# jarit__paneli.net
KiCad netlist of a schematic drawn in Altium Designer
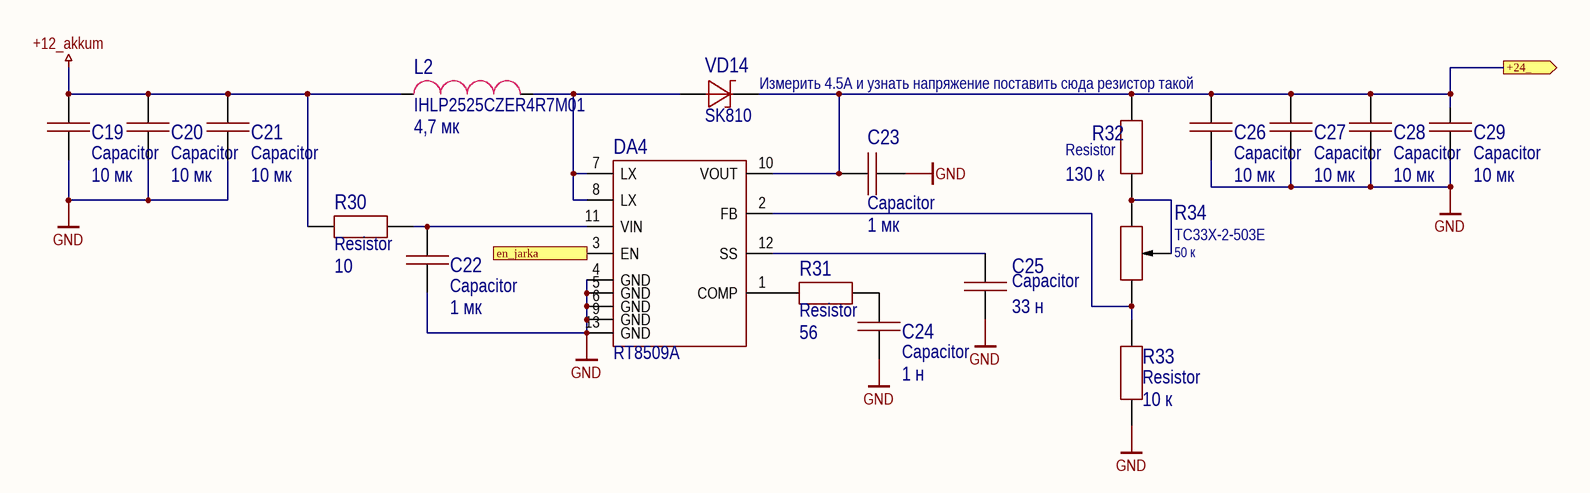
[diagram p0: jarit'_paneli.SchDoc]

(export (version "E")
  (design (tool "Eeschema 10.0.6"))
  (components
    (comp (ref "C19")
      (value "Capacitor")
      (footprint "1210C")
      (description "Конденсатор")
      (fields
        (field (name "ALTIUM_VALUE") "10 мк")
        (field (name "PART NUMBER") "Capacitor_10u_10_35V_X7R_1210C")
        (field (name "TOLERANCE") "0,1")
      )
      (libsource (lib "Hydrolib") (part "Capacitor"))
    )
    (comp (ref "C20")
      (value "Capacitor")
      (footprint "1210C")
      (description "Конденсатор")
      (fields
        (field (name "ALTIUM_VALUE") "10 мк")
        (field (name "PART NUMBER") "Capacitor_10u_10_35V_X7R_1210C")
        (field (name "TOLERANCE") "0,1")
      )
      (libsource (lib "Hydrolib") (part "Capacitor"))
    )
    (comp (ref "C21")
      (value "Capacitor")
      (footprint "1210C")
      (description "Конденсатор")
      (fields
        (field (name "ALTIUM_VALUE") "10 мк")
        (field (name "PART NUMBER") "Capacitor_10u_10_35V_X7R_1210C")
        (field (name "TOLERANCE") "0,1")
      )
      (libsource (lib "Hydrolib") (part "Capacitor"))
    )
    (comp (ref "C22")
      (value "Capacitor")
      (footprint "0603C")
      (description "Конденсатор")
      (fields
        (field (name "ALTIUM_VALUE") "1 мк")
        (field (name "PART NUMBER") "Capacitor_1u_10_50V_X7R_0603C")
        (field (name "TOLERANCE") "0,1")
      )
      (libsource (lib "Hydrolib") (part "Capacitor"))
    )
    (comp (ref "C23")
      (value "Capacitor")
      (footprint "0603C")
      (description "Конденсатор")
      (fields
        (field (name "ALTIUM_VALUE") "1 мк")
        (field (name "PART NUMBER") "Capacitor_1u_10_50V_X7R_0603C")
        (field (name "TOLERANCE") "0,1")
      )
      (libsource (lib "Hydrolib") (part "Capacitor"))
    )
    (comp (ref "C24")
      (value "Capacitor")
      (footprint "0603C")
      (description "Конденсатор")
      (fields
        (field (name "ALTIUM_VALUE") "1 н")
        (field (name "PART NUMBER") "Capacitor_1n_10_50V_X7R_0603C")
        (field (name "TOLERANCE") "0,1")
      )
      (libsource (lib "Hydrolib") (part "Capacitor"))
    )
    (comp (ref "C25")
      (value "Capacitor")
      (footprint "0603C")
      (description "Конденсатор")
      (fields
        (field (name "ALTIUM_VALUE") "33 н")
        (field (name "PART NUMBER") "Capacitor_33n_10_50V_X7R_0603C")
        (field (name "TOLERANCE") "0,1")
      )
      (libsource (lib "Hydrolib") (part "Capacitor"))
    )
    (comp (ref "C26")
      (value "Capacitor")
      (footprint "1210C")
      (description "Конденсатор")
      (fields
        (field (name "ALTIUM_VALUE") "10 мк")
        (field (name "PART NUMBER") "Capacitor_10u_10_35V_X7R_1210C")
        (field (name "TOLERANCE") "0,1")
      )
      (libsource (lib "Hydrolib") (part "Capacitor"))
    )
    (comp (ref "C27")
      (value "Capacitor")
      (footprint "1210C")
      (description "Конденсатор")
      (fields
        (field (name "ALTIUM_VALUE") "10 мк")
        (field (name "PART NUMBER") "Capacitor_10u_10_35V_X7R_1210C")
        (field (name "TOLERANCE") "0,1")
      )
      (libsource (lib "Hydrolib") (part "Capacitor"))
    )
    (comp (ref "C28")
      (value "Capacitor")
      (footprint "1210C")
      (description "Конденсатор")
      (fields
        (field (name "ALTIUM_VALUE") "10 мк")
        (field (name "PART NUMBER") "Capacitor_10u_10_35V_X7R_1210C")
        (field (name "TOLERANCE") "0,1")
      )
      (libsource (lib "Hydrolib") (part "Capacitor"))
    )
    (comp (ref "C29")
      (value "Capacitor")
      (footprint "1210C")
      (description "Конденсатор")
      (fields
        (field (name "ALTIUM_VALUE") "10 мк")
        (field (name "PART NUMBER") "Capacitor_10u_10_35V_X7R_1210C")
        (field (name "TOLERANCE") "0,1")
      )
      (libsource (lib "Hydrolib") (part "Capacitor"))
    )
    (comp (ref "DA4")
      (value "RT8509A")
      (footprint "WDFN5x5-12")
      (description "Импульсный повышающий DC-DC стабилизатор, регулируемый, 2.8В-14В (Vin), 24В/4.5A, 1.5МГц, WDFN-12")
      (libsource (lib "Hydrolib") (part "RT8509A"))
    )
    (comp (ref "L2")
      (value "IHLP2525CZER4R7M01")
      (footprint "IHLP-2525")
      (description "ЧИП-индуктивность экранированная 4,7мкГн ±20% 5,5A 40мОм 2525")
      (fields (field (name "ALTIUM_VALUE") "4,7 мк"))
      (libsource (lib "Hydrolib") (part "Inductance"))
    )
    (comp (ref "R30")
      (value "Resistor")
      (footprint "0603R")
      (description "Резистор номиналом 10 Ом и точностью 1%")
      (fields
        (field (name "ALTIUM_VALUE") "10")
        (field (name "PART NUMBER") "Resistor_10_1_0603")
        (field (name "TOLERANCE") "1%")
      )
      (libsource (lib "") (part "Resistor_2"))
    )
    (comp (ref "R31")
      (value "Resistor")
      (footprint "0603R")
      (description "Резистор номиналом 56 Ом и точностью 1%")
      (fields
        (field (name "ALTIUM_VALUE") "56")
        (field (name "PART NUMBER") "Resistor_56_1_0603")
        (field (name "TOLERANCE") "1%")
      )
      (libsource (lib "") (part "Resistor_1"))
    )
    (comp (ref "R32")
      (value "Resistor")
      (footprint "0603R")
      (description "Резистор номиналом 130 кОм и точностью 1%")
      (fields
        (field (name "ALTIUM_VALUE") "130 к")
        (field (name "PART NUMBER") "Resistor_130k_1_0603")
        (field (name "TOLERANCE") "1%")
      )
      (libsource (lib "") (part "Resistor_3"))
    )
    (comp (ref "R33")
      (value "Resistor")
      (footprint "0603R")
      (description "Резистор номиналом 10 кОм и точностью 1%")
      (fields
        (field (name "ALTIUM_VALUE") "10 к")
        (field (name "PART NUMBER") "Resistor_10k_1_0603")
        (field (name "TOLERANCE") "1%")
      )
      (libsource (lib "Hydrolib") (part "Resistor"))
    )
    (comp (ref "R34")
      (value "TC33X-2-503E")
      (footprint "3mm_trim")
      (description "Потенциометр однооборотный керметный 50кОм 0.1Вт ±25% SMD лента на катушке")
      (fields (field (name "ALTIUM_VALUE") "50 к") (field (name "TOLERANCE") "50%"))
      (libsource (lib "Hydrolib") (part "trim_res"))
    )
    (comp (ref "VD14")
      (value "SK810")
      (footprint "SMC")
      (description "Диод шоттки на 100 В, ном. ток 8 А")
      (libsource (lib "Hydrolib") (part "Schottky_diode"))
    )
  )
  (nets
    (net (code "1") (name "+12_akkum") (class "Default")
      (node (ref "C19") (pin "2") (pinfunction "2_2") (pintype "passive"))
      (node (ref "C20") (pin "2") (pinfunction "2_2") (pintype "passive"))
      (node (ref "C21") (pin "2") (pinfunction "2_2") (pintype "passive"))
      (node (ref "L2") (pin "1") (pinfunction "1_1") (pintype "passive"))
      (node (ref "R30") (pin "2") (pinfunction "2_2") (pintype "passive"))
    )
    (net (code "2") (name "/+24_") (class "Default")
      (node (ref "C23") (pin "1") (pinfunction "1_1") (pintype "passive"))
      (node (ref "C26") (pin "2") (pinfunction "2_2") (pintype "passive"))
      (node (ref "C27") (pin "2") (pinfunction "2_2") (pintype "passive"))
      (node (ref "C28") (pin "2") (pinfunction "2_2") (pintype "passive"))
      (node (ref "C29") (pin "2") (pinfunction "2_2") (pintype "passive"))
      (node (ref "DA4") (pin "10") (pinfunction "VOUT_10") (pintype "passive"))
      (node (ref "R32") (pin "2") (pinfunction "2_2") (pintype "passive"))
      (node (ref "VD14") (pin "2") (pinfunction "2_2") (pintype "passive"))
    )
    (net (code "3") (name "/en_jarka") (class "Default")
      (node (ref "DA4") (pin "3") (pinfunction "EN_3") (pintype "passive"))
    )
    (net (code "4") (name "GND") (class "Default")
      (node (ref "C19") (pin "1") (pinfunction "1_1") (pintype "passive"))
      (node (ref "C20") (pin "1") (pinfunction "1_1") (pintype "passive"))
      (node (ref "C21") (pin "1") (pinfunction "1_1") (pintype "passive"))
      (node (ref "C22") (pin "1") (pinfunction "1_1") (pintype "passive"))
      (node (ref "C23") (pin "2") (pinfunction "2_2") (pintype "passive"))
      (node (ref "C24") (pin "1") (pinfunction "1_1") (pintype "passive"))
      (node (ref "C25") (pin "2") (pinfunction "2_2") (pintype "passive"))
      (node (ref "C26") (pin "1") (pinfunction "1_1") (pintype "passive"))
      (node (ref "C27") (pin "1") (pinfunction "1_1") (pintype "passive"))
      (node (ref "C28") (pin "1") (pinfunction "1_1") (pintype "passive"))
      (node (ref "C29") (pin "1") (pinfunction "1_1") (pintype "passive"))
      (node (ref "DA4") (pin "13") (pinfunction "GND_13") (pintype "passive"))
      (node (ref "DA4") (pin "4") (pinfunction "GND_4") (pintype "passive"))
      (node (ref "DA4") (pin "5") (pinfunction "GND_5") (pintype "passive"))
      (node (ref "DA4") (pin "6") (pinfunction "GND_6") (pintype "passive"))
      (node (ref "DA4") (pin "9") (pinfunction "GND_9") (pintype "passive"))
      (node (ref "R33") (pin "2") (pinfunction "2_2") (pintype "passive"))
    )
    (net (code "5") (name "Net-(C24-Pad2)") (class "Default")
      (node (ref "C24") (pin "2") (pinfunction "2_2") (pintype "passive"))
      (node (ref "R31") (pin "2") (pinfunction "2_2") (pintype "passive"))
    )
    (net (code "6") (name "Net-(DA4-COMP)") (class "Default")
      (node (ref "DA4") (pin "1") (pinfunction "COMP_1") (pintype "passive"))
      (node (ref "R31") (pin "1") (pinfunction "1_1") (pintype "passive"))
    )
    (net (code "7") (name "Net-(DA4-FB)") (class "Default")
      (node (ref "DA4") (pin "2") (pinfunction "FB_2") (pintype "passive"))
      (node (ref "R33") (pin "1") (pinfunction "1_1") (pintype "passive"))
      (node (ref "R34") (pin "3") (pinfunction "3_3") (pintype "passive"))
    )
    (net (code "8") (name "Net-(DA4-LX-Pad7)") (class "Default")
      (node (ref "DA4") (pin "7") (pinfunction "LX_7") (pintype "passive"))
      (node (ref "DA4") (pin "8") (pinfunction "LX_8") (pintype "passive"))
      (node (ref "L2") (pin "2") (pinfunction "2_2") (pintype "passive"))
      (node (ref "VD14") (pin "1") (pinfunction "1_1") (pintype "passive"))
    )
    (net (code "9") (name "Net-(DA4-SS)") (class "Default")
      (node (ref "C25") (pin "1") (pinfunction "1_1") (pintype "passive"))
      (node (ref "DA4") (pin "12") (pinfunction "SS_12") (pintype "passive"))
    )
    (net (code "10") (name "Net-(DA4-VIN)") (class "Default")
      (node (ref "C22") (pin "2") (pinfunction "2_2") (pintype "passive"))
      (node (ref "DA4") (pin "11") (pinfunction "VIN_11") (pintype "passive"))
      (node (ref "R30") (pin "1") (pinfunction "1_1") (pintype "passive"))
    )
    (net (code "11") (name "Net-(R32-Pad1)") (class "Default")
      (node (ref "R32") (pin "1") (pinfunction "1_1") (pintype "passive"))
      (node (ref "R34") (pin "1") (pinfunction "1_1") (pintype "passive"))
      (node (ref "R34") (pin "2") (pinfunction "2_2") (pintype "passive"))
    )
  )
)
